# Core_nRF52840.net
KiCad netlist of a schematic drawn in Altium Designer
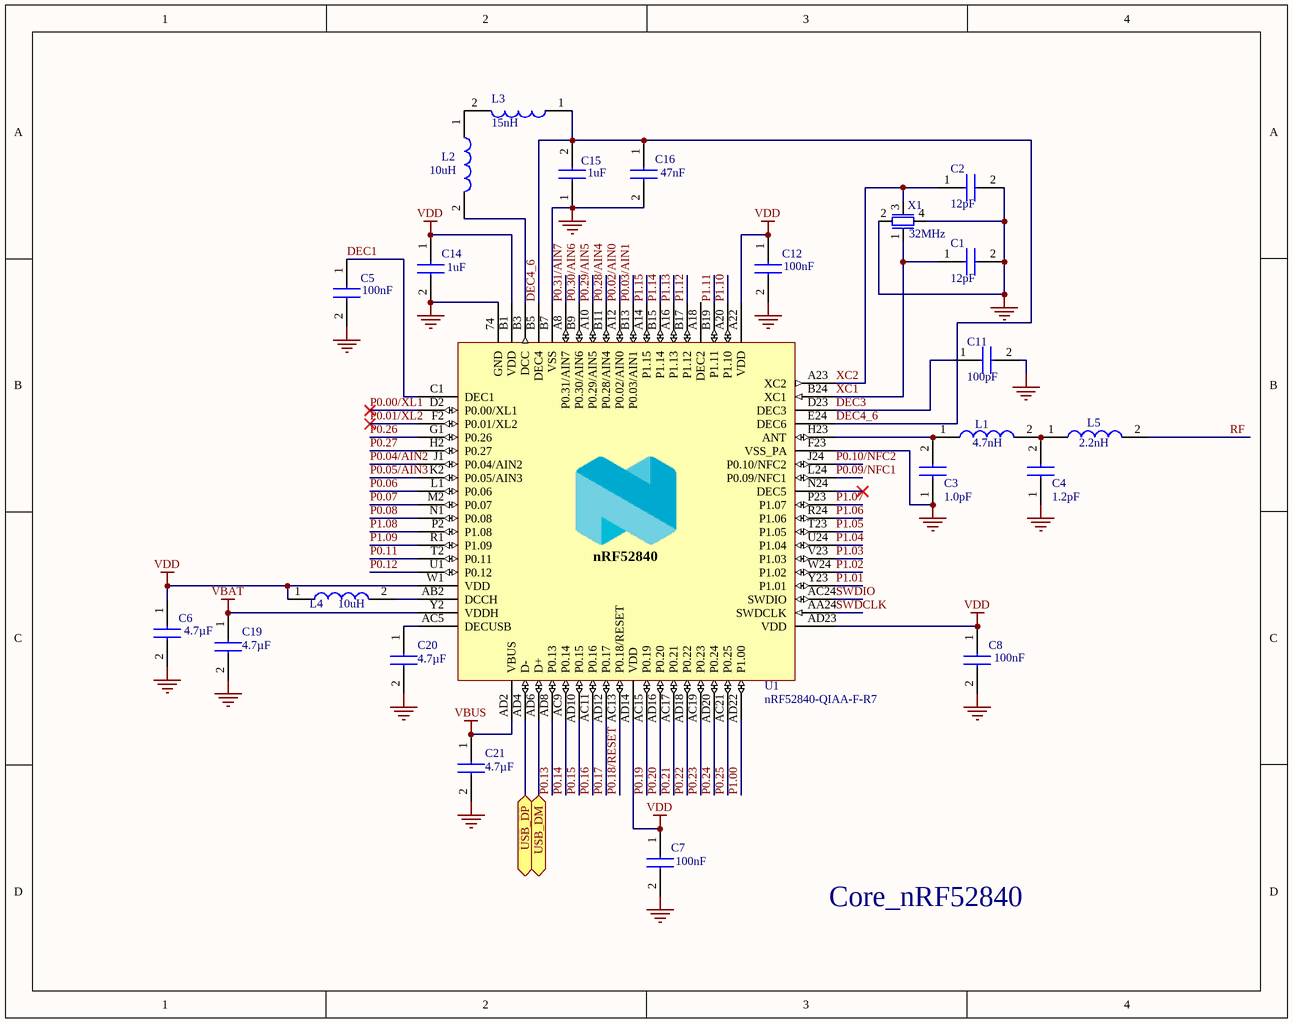
[diagram p0: Core_nRF52840.SchDoc]

(export (version "E")
  (design (tool "Eeschema 10.0.6"))
  (components
    (comp (ref "C1")
      (value "12pF")
      (footprint "BoatRC:GCM155")
      (description "12 pF C0G ±1% 50 V")
      (fields (field (name "MANUFACTURER_PART_NUMBER") "GCM1555C1H120FA16D"))
      (libsource (lib "BoatRC") (part "C_12pF_0402_C0G_1pct"))
    )
    (comp (ref "C2")
      (value "12pF")
      (footprint "BoatRC:GCM155")
      (description "12 pF C0G ±1% 50 V")
      (fields (field (name "MANUFACTURER_PART_NUMBER") "GCM1555C1H120FA16D"))
      (libsource (lib "BoatRC") (part "C_12pF_0402_C0G_1pct"))
    )
    (comp (ref "C3")
      (value "1.0pF")
      (footprint "BoatRC:CAPC1005X55N")
      (description "1.0 pF C0G ±0.05 pF high-Q")
      (fields (field (name "MANUFACTURER_PART_NUMBER") "GJM1555C1H1R0WB01D"))
      (libsource (lib "BoatRC") (part "C_1p0pF_0402_C0G_HQ"))
    )
    (comp (ref "C4")
      (value "1.2pF")
      (footprint "BoatRC:CAPC1005X55N")
      (description "1.2 pF C0G ±0.05 pF high-Q")
      (fields (field (name "MANUFACTURER_PART_NUMBER") "GJM1555C1H1R2WB01D"))
      (libsource (lib "BoatRC") (part "C_1p2pF_0402_C0G_HQ"))
    )
    (comp (ref "C5")
      (value "100nF")
      (footprint "BoatRC:RESC1005X55N")
      (description "100 nF X7R ±10% 50 V")
      (fields (field (name "MANUFACTURER_PART_NUMBER") "CL05B104KB54PNC"))
      (libsource (lib "BoatRC") (part "C_100nF_0402_X7R_50V"))
    )
    (comp (ref "C6")
      (value "4.7µF")
      (footprint "BoatRC:GRM18x")
      (description "4.7 µF X7R ±10% 16 V")
      (fields (field (name "MANUFACTURER_PART_NUMBER") "GRM188Z71C475KE21D"))
      (libsource (lib "BoatRC") (part "C_4u7F_0603_X7R_16V"))
    )
    (comp (ref "C7")
      (value "100nF")
      (footprint "BoatRC:RESC1005X55N")
      (description "100 nF X7R ±10% 50 V")
      (fields (field (name "MANUFACTURER_PART_NUMBER") "CL05B104KB54PNC"))
      (libsource (lib "BoatRC") (part "C_100nF_0402_X7R_50V"))
    )
    (comp (ref "C8")
      (value "100nF")
      (footprint "BoatRC:RESC1005X55N")
      (description "100 nF X7R ±10% 50 V")
      (fields (field (name "MANUFACTURER_PART_NUMBER") "CL05B104KB54PNC"))
      (libsource (lib "BoatRC") (part "C_100nF_0402_X7R_50V"))
    )
    (comp (ref "C11")
      (value "100pF")
      (footprint "BoatRC:CAPC1005X55N")
      (description "100 pF C0G ±5% 50 V")
      (fields (field (name "MANUFACTURER_PART_NUMBER") "0402CG101J500NT"))
      (libsource (lib "BoatRC") (part "C_100pF_0402_C0G"))
    )
    (comp (ref "C12")
      (value "100nF")
      (footprint "BoatRC:RESC1005X55N")
      (description "100 nF X7R ±10% 50 V")
      (fields (field (name "MANUFACTURER_PART_NUMBER") "CL05B104KB54PNC"))
      (libsource (lib "BoatRC") (part "C_100nF_0402_X7R_50V"))
    )
    (comp (ref "C14")
      (value "1uF")
      (footprint "BoatRC:CAPC1608X95N")
      (description "1.0 µF X7R ±10% 50 V")
      (fields (field (name "MANUFACTURER_PART_NUMBER") "CL10B105KB8NQNC"))
      (libsource (lib "BoatRC") (part "C_1uF_0603_X7R_50V"))
    )
    (comp (ref "C15")
      (value "1uF")
      (footprint "BoatRC:CAPC1608X95N")
      (description "1.0 µF X7R ±10% 50 V")
      (fields (field (name "MANUFACTURER_PART_NUMBER") "CL10B105KB8NQNC"))
      (libsource (lib "BoatRC") (part "C_1uF_0603_X7R_50V"))
    )
    (comp (ref "C16")
      (value "47nF")
      (footprint "BoatRC:CAPC1005X55N")
      (description "47 nF X7R ±10% 50 V")
      (fields (field (name "MANUFACTURER_PART_NUMBER") "CC0402KRX7R9BB473"))
      (libsource (lib "BoatRC") (part "C_47nF_0402_X7R_50V"))
    )
    (comp (ref "C19")
      (value "4.7µF")
      (footprint "BoatRC:GRM18x")
      (description "4.7 µF X7R ±10% 16 V")
      (fields (field (name "MANUFACTURER_PART_NUMBER") "GRM188Z71C475KE21D"))
      (libsource (lib "BoatRC") (part "C_4u7F_0603_X7R_16V"))
    )
    (comp (ref "C20")
      (value "4.7µF")
      (footprint "BoatRC:GRM18x")
      (description "4.7 µF X7R ±10% 16 V")
      (fields (field (name "MANUFACTURER_PART_NUMBER") "GRM188Z71C475KE21D"))
      (libsource (lib "BoatRC") (part "C_4u7F_0603_X7R_16V"))
    )
    (comp (ref "C21")
      (value "4.7µF")
      (footprint "BoatRC:GRM18x")
      (description "4.7 µF X7R ±10% 16 V")
      (fields (field (name "MANUFACTURER_PART_NUMBER") "GRM188Z71C475KE21D"))
      (libsource (lib "BoatRC") (part "C_4u7F_0603_X7R_16V"))
    )
    (comp (ref "L1")
      (value "4.7nH")
      (footprint "BoatRC:LQG15WH0N7B02D")
      (description "4.7 nH ±0.1 nH RF")
      (fields (field (name "MANUFACTURER_PART_NUMBER") "LQG15HN4N7B02D"))
      (libsource (lib "BoatRC") (part "L_4n7H_0402_RF"))
    )
    (comp (ref "L2")
      (value "10uH")
      (footprint "BoatRC:CAPC1608X95N")
      (description "10 µH ±20%, 400 mA, 0.55 Ω")
      (fields (field (name "MANUFACTURER_PART_NUMBER") "MGFL1608F100MT-LF"))
      (libsource (lib "BoatRC") (part "L_10uH_0603"))
    )
    (comp (ref "L3")
      (value "15nH")
      (footprint "BoatRC:LQG15WH0N7B02D")
      (description "15 nH ±5%, 450 mA")
      (fields (field (name "MANUFACTURER_PART_NUMBER") "LQG15HS2N2B02D"))
      (libsource (lib "BoatRC") (part "L_15nH_0402"))
    )
    (comp (ref "L4")
      (value "10uH")
      (footprint "BoatRC:CAPC1608X95N")
      (description "10 µH ±20%, 400 mA, 0.55 Ω")
      (fields (field (name "MANUFACTURER_PART_NUMBER") "MGFL1608F100MT-LF"))
      (libsource (lib "BoatRC") (part "L_10uH_0603"))
    )
    (comp (ref "L5")
      (value "2.2nH")
      (footprint "BoatRC:LQG15WH0N7B02D")
      (description "2.2 nH ±0.1 nH RF")
      (fields (field (name "MANUFACTURER_PART_NUMBER") "LQG15HS15NJ02D"))
      (libsource (lib "BoatRC") (part "L_2n2H_0402_RF"))
    )
    (comp (ref "U1")
      (value "nRF52840-QIAA-F-R7")
      (footprint "AQFN50P700X700X85_HS-74N")
      (description "Multi-protocol Bluetooth Low Energy, IEEE 802.15.4, ANT and 2.4GHz proprietary system-on-chip")
      (fields
        (field (name "MANUFACTURER") "Nordic Semiconductor")
        (field (name "DIGIKEY PART NUMBER") "4823-NRF52840-QIAA-F-R7CT-ND")
      )
      (libsource (lib "BoatRC") (part "nRF52840-QIAA-F-R7"))
    )
    (comp (ref "X1")
      (value "32MHz")
      (footprint "BoatRC:X201632MKB4SI")
      (description "32 MHz, 8 pF, ±10/±20 ppm")
      (fields (field (name "MANUFACTURER_PART_NUMBER") "X201632MKB4SI"))
      (libsource (lib "BoatRC") (part "Y_32MHz_2016_8pF"))
    )
  )
  (nets
    (net (code "1") (name "/DEC1") (class "Default")
      (node (ref "C5") (pin "1") (pinfunction "1_1") (pintype "passive"))
      (node (ref "U1") (pin "C1") (pinfunction "DEC1_C1") (pintype "power_in"))
    )
    (net (code "2") (name "/DEC3") (class "Default")
      (node (ref "C11") (pin "1") (pinfunction "1_1") (pintype "passive"))
      (node (ref "U1") (pin "D23") (pinfunction "DEC3_D23") (pintype "power_in"))
    )
    (net (code "3") (name "/DEC4_6") (class "Default")
      (node (ref "C15") (pin "2") (pinfunction "2_2") (pintype "passive"))
      (node (ref "C16") (pin "1") (pinfunction "1_1") (pintype "passive"))
      (node (ref "L3") (pin "1") (pinfunction "1_1") (pintype "passive"))
      (node (ref "U1") (pin "B5") (pinfunction "DEC4_B5") (pintype "power_in"))
      (node (ref "U1") (pin "E24") (pinfunction "DEC6_E24") (pintype "power_in"))
    )
    (net (code "4") (name "/P0.00{slash}XL1") (class "Default")
      (node (ref "U1") (pin "D2") (pinfunction "P0.00/XL1_D2") (pintype "bidirectional+no_connect"))
    )
    (net (code "5") (name "/P0.01{slash}XL2") (class "Default")
      (node (ref "U1") (pin "F2") (pinfunction "P0.01/XL2_F2") (pintype "bidirectional+no_connect"))
    )
    (net (code "6") (name "/P0.02{slash}AIN0") (class "Default")
      (node (ref "U1") (pin "A12") (pinfunction "P0.02/AIN0_A12") (pintype "bidirectional"))
    )
    (net (code "7") (name "/P0.03{slash}AIN1") (class "Default")
      (node (ref "U1") (pin "B13") (pinfunction "P0.03/AIN1_B13") (pintype "bidirectional"))
    )
    (net (code "8") (name "/P0.04{slash}AIN2") (class "Default")
      (node (ref "U1") (pin "J1") (pinfunction "P0.04/AIN2_J1") (pintype "bidirectional"))
    )
    (net (code "9") (name "/P0.05{slash}AIN3") (class "Default")
      (node (ref "U1") (pin "K2") (pinfunction "P0.05/AIN3_K2") (pintype "bidirectional"))
    )
    (net (code "10") (name "/P0.06") (class "Default")
      (node (ref "U1") (pin "L1") (pinfunction "P0.06_L1") (pintype "bidirectional"))
    )
    (net (code "11") (name "/P0.07") (class "Default")
      (node (ref "U1") (pin "M2") (pinfunction "P0.07_M2") (pintype "bidirectional"))
    )
    (net (code "12") (name "/P0.08") (class "Default")
      (node (ref "U1") (pin "N1") (pinfunction "P0.08_N1") (pintype "bidirectional"))
    )
    (net (code "13") (name "/P0.09{slash}NFC1") (class "Default")
      (node (ref "U1") (pin "L24") (pinfunction "P0.09/NFC1_L24") (pintype "bidirectional"))
    )
    (net (code "14") (name "/P0.10{slash}NFC2") (class "Default")
      (node (ref "U1") (pin "J24") (pinfunction "P0.10/NFC2_J24") (pintype "bidirectional"))
    )
    (net (code "15") (name "/P0.11") (class "Default")
      (node (ref "U1") (pin "T2") (pinfunction "P0.11_T2") (pintype "bidirectional"))
    )
    (net (code "16") (name "/P0.12") (class "Default")
      (node (ref "U1") (pin "U1") (pinfunction "P0.12_U1") (pintype "bidirectional"))
    )
    (net (code "17") (name "/P0.13") (class "Default")
      (node (ref "U1") (pin "AD8") (pinfunction "P0.13_AD8") (pintype "bidirectional"))
    )
    (net (code "18") (name "/P0.14") (class "Default")
      (node (ref "U1") (pin "AC9") (pinfunction "P0.14_AC9") (pintype "bidirectional"))
    )
    (net (code "19") (name "/P0.15") (class "Default")
      (node (ref "U1") (pin "AD10") (pinfunction "P0.15_AD10") (pintype "bidirectional"))
    )
    (net (code "20") (name "/P0.16") (class "Default")
      (node (ref "U1") (pin "AC11") (pinfunction "P0.16_AC11") (pintype "bidirectional"))
    )
    (net (code "21") (name "/P0.17") (class "Default")
      (node (ref "U1") (pin "AD12") (pinfunction "P0.17_AD12") (pintype "bidirectional"))
    )
    (net (code "22") (name "/P0.18{slash}RESET") (class "Default")
      (node (ref "U1") (pin "AC13") (pinfunction "P0.18/RESET_AC13") (pintype "bidirectional"))
    )
    (net (code "23") (name "/P0.19") (class "Default")
      (node (ref "U1") (pin "AC15") (pinfunction "P0.19_AC15") (pintype "bidirectional"))
    )
    (net (code "24") (name "/P0.20") (class "Default")
      (node (ref "U1") (pin "AD16") (pinfunction "P0.20_AD16") (pintype "bidirectional"))
    )
    (net (code "25") (name "/P0.21") (class "Default")
      (node (ref "U1") (pin "AC17") (pinfunction "P0.21_AC17") (pintype "bidirectional"))
    )
    (net (code "26") (name "/P0.22") (class "Default")
      (node (ref "U1") (pin "AD18") (pinfunction "P0.22_AD18") (pintype "bidirectional"))
    )
    (net (code "27") (name "/P0.23") (class "Default")
      (node (ref "U1") (pin "AC19") (pinfunction "P0.23_AC19") (pintype "bidirectional"))
    )
    (net (code "28") (name "/P0.24") (class "Default")
      (node (ref "U1") (pin "AD20") (pinfunction "P0.24_AD20") (pintype "bidirectional"))
    )
    (net (code "29") (name "/P0.25") (class "Default")
      (node (ref "U1") (pin "AC21") (pinfunction "P0.25_AC21") (pintype "bidirectional"))
    )
    (net (code "30") (name "/P0.26") (class "Default")
      (node (ref "U1") (pin "G1") (pinfunction "P0.26_G1") (pintype "bidirectional"))
    )
    (net (code "31") (name "/P0.27") (class "Default")
      (node (ref "U1") (pin "H2") (pinfunction "P0.27_H2") (pintype "bidirectional"))
    )
    (net (code "32") (name "/P0.28{slash}AIN4") (class "Default")
      (node (ref "U1") (pin "B11") (pinfunction "P0.28/AIN4_B11") (pintype "bidirectional"))
    )
    (net (code "33") (name "/P0.29{slash}AIN5") (class "Default")
      (node (ref "U1") (pin "A10") (pinfunction "P0.29/AIN5_A10") (pintype "bidirectional"))
    )
    (net (code "34") (name "/P0.30{slash}AIN6") (class "Default")
      (node (ref "U1") (pin "B9") (pinfunction "P0.30/AIN6_B9") (pintype "bidirectional"))
    )
    (net (code "35") (name "/P0.31{slash}AIN7") (class "Default")
      (node (ref "U1") (pin "A8") (pinfunction "P0.31/AIN7_A8") (pintype "bidirectional"))
    )
    (net (code "36") (name "/P1.00") (class "Default")
      (node (ref "U1") (pin "AD22") (pinfunction "P1.00_AD22") (pintype "bidirectional"))
    )
    (net (code "37") (name "/P1.01") (class "Default")
      (node (ref "U1") (pin "Y23") (pinfunction "P1.01_Y23") (pintype "bidirectional"))
    )
    (net (code "38") (name "/P1.02") (class "Default")
      (node (ref "U1") (pin "W24") (pinfunction "P1.02_W24") (pintype "bidirectional"))
    )
    (net (code "39") (name "/P1.03") (class "Default")
      (node (ref "U1") (pin "V23") (pinfunction "P1.03_V23") (pintype "bidirectional"))
    )
    (net (code "40") (name "/P1.04") (class "Default")
      (node (ref "U1") (pin "U24") (pinfunction "P1.04_U24") (pintype "bidirectional"))
    )
    (net (code "41") (name "/P1.05") (class "Default")
      (node (ref "U1") (pin "T23") (pinfunction "P1.05_T23") (pintype "bidirectional"))
    )
    (net (code "42") (name "/P1.06") (class "Default")
      (node (ref "U1") (pin "R24") (pinfunction "P1.06_R24") (pintype "bidirectional"))
    )
    (net (code "43") (name "/P1.07") (class "Default")
      (node (ref "U1") (pin "P23") (pinfunction "P1.07_P23") (pintype "bidirectional"))
    )
    (net (code "44") (name "/P1.08") (class "Default")
      (node (ref "U1") (pin "P2") (pinfunction "P1.08_P2") (pintype "bidirectional"))
    )
    (net (code "45") (name "/P1.09") (class "Default")
      (node (ref "U1") (pin "R1") (pinfunction "P1.09_R1") (pintype "bidirectional"))
    )
    (net (code "46") (name "/P1.10") (class "Default")
      (node (ref "U1") (pin "A20") (pinfunction "P1.10_A20") (pintype "bidirectional"))
    )
    (net (code "47") (name "/P1.11") (class "Default")
      (node (ref "U1") (pin "B19") (pinfunction "P1.11_B19") (pintype "bidirectional"))
    )
    (net (code "48") (name "/P1.12") (class "Default")
      (node (ref "U1") (pin "B17") (pinfunction "P1.12_B17") (pintype "bidirectional"))
    )
    (net (code "49") (name "/P1.13") (class "Default")
      (node (ref "U1") (pin "A16") (pinfunction "P1.13_A16") (pintype "bidirectional"))
    )
    (net (code "50") (name "/P1.14") (class "Default")
      (node (ref "U1") (pin "B15") (pinfunction "P1.14_B15") (pintype "bidirectional"))
    )
    (net (code "51") (name "/P1.15") (class "Default")
      (node (ref "U1") (pin "A14") (pinfunction "P1.15_A14") (pintype "bidirectional"))
    )
    (net (code "52") (name "/RF") (class "Default")
      (node (ref "L5") (pin "2") (pinfunction "2_2") (pintype "passive"))
    )
    (net (code "53") (name "/SWDCLK") (class "Default")
      (node (ref "U1") (pin "AA24") (pinfunction "SWDCLK_AA24") (pintype "input"))
    )
    (net (code "54") (name "/SWDIO") (class "Default")
      (node (ref "U1") (pin "AC24") (pinfunction "SWDIO_AC24") (pintype "bidirectional"))
    )
    (net (code "55") (name "/USB_DM") (class "Default")
      (node (ref "U1") (pin "AD6") (pinfunction "D+_AD6") (pintype "bidirectional"))
    )
    (net (code "56") (name "/USB_DP") (class "Default")
      (node (ref "U1") (pin "AD4") (pinfunction "D-_AD4") (pintype "bidirectional"))
    )
    (net (code "57") (name "/XC1") (class "Default")
      (node (ref "C1") (pin "1") (pinfunction "1_1") (pintype "passive"))
      (node (ref "U1") (pin "B24") (pinfunction "XC1_B24") (pintype "input"))
      (node (ref "X1") (pin "1") (pinfunction "inp_1") (pintype "passive"))
    )
    (net (code "58") (name "/XC2") (class "Default")
      (node (ref "C2") (pin "1") (pinfunction "1_1") (pintype "passive"))
      (node (ref "U1") (pin "A23") (pinfunction "XC2_A23") (pintype "output"))
      (node (ref "X1") (pin "3") (pinfunction "out_3") (pintype "passive"))
    )
    (net (code "59") (name "GND") (class "Default")
      (node (ref "C1") (pin "2") (pinfunction "2_2") (pintype "passive"))
      (node (ref "C11") (pin "2") (pinfunction "2_2") (pintype "passive"))
      (node (ref "C12") (pin "2") (pinfunction "2_2") (pintype "passive"))
      (node (ref "C14") (pin "2") (pinfunction "2_2") (pintype "passive"))
      (node (ref "C15") (pin "1") (pinfunction "1_1") (pintype "passive"))
      (node (ref "C16") (pin "2") (pinfunction "2_2") (pintype "passive"))
      (node (ref "C19") (pin "2") (pinfunction "2_2") (pintype "passive"))
      (node (ref "C2") (pin "2") (pinfunction "2_2") (pintype "passive"))
      (node (ref "C20") (pin "2") (pinfunction "2_2") (pintype "passive"))
      (node (ref "C21") (pin "2") (pinfunction "2_2") (pintype "passive"))
      (node (ref "C3") (pin "1") (pinfunction "1_1") (pintype "passive"))
      (node (ref "C4") (pin "1") (pinfunction "1_1") (pintype "passive"))
      (node (ref "C5") (pin "2") (pinfunction "2_2") (pintype "passive"))
      (node (ref "C6") (pin "2") (pinfunction "2_2") (pintype "passive"))
      (node (ref "C7") (pin "2") (pinfunction "2_2") (pintype "passive"))
      (node (ref "C8") (pin "2") (pinfunction "2_2") (pintype "passive"))
      (node (ref "U1") (pin "74") (pinfunction "GND_74") (pintype "power_in"))
      (node (ref "U1") (pin "B7") (pinfunction "VSS_B7") (pintype "power_in"))
      (node (ref "U1") (pin "F23") (pinfunction "VSS_PA_F23") (pintype "power_in"))
      (node (ref "X1") (pin "2") (pinfunction "GND_2") (pintype "passive"))
      (node (ref "X1") (pin "4") (pinfunction "GND_4") (pintype "passive"))
    )
    (net (code "60") (name "Net-(C4-Pad2)") (class "Default")
      (node (ref "C4") (pin "2") (pinfunction "2_2") (pintype "passive"))
      (node (ref "L1") (pin "2") (pinfunction "2_2") (pintype "passive"))
      (node (ref "L5") (pin "1") (pinfunction "1_1") (pintype "passive"))
    )
    (net (code "61") (name "Net-(L2-Pad1)") (class "Default")
      (node (ref "L2") (pin "1") (pinfunction "1_1") (pintype "passive"))
      (node (ref "L3") (pin "2") (pinfunction "2_2") (pintype "passive"))
    )
    (net (code "62") (name "Net-(U1-ANT)") (class "Default")
      (node (ref "C3") (pin "2") (pinfunction "2_2") (pintype "passive"))
      (node (ref "L1") (pin "1") (pinfunction "1_1") (pintype "passive"))
      (node (ref "U1") (pin "H23") (pinfunction "ANT_H23") (pintype "bidirectional"))
    )
    (net (code "63") (name "Net-(U1-DCC)") (class "Default")
      (node (ref "L2") (pin "2") (pinfunction "2_2") (pintype "passive"))
      (node (ref "U1") (pin "B3") (pinfunction "DCC_B3") (pintype "output"))
    )
    (net (code "64") (name "Net-(U1-DCCH)") (class "Default")
      (node (ref "L4") (pin "2") (pinfunction "2_2") (pintype "passive"))
      (node (ref "U1") (pin "AB2") (pinfunction "DCCH_AB2") (pintype "power_in"))
    )
    (net (code "65") (name "Net-(U1-DECUSB)") (class "Default")
      (node (ref "C20") (pin "1") (pinfunction "1_1") (pintype "passive"))
      (node (ref "U1") (pin "AC5") (pinfunction "DECUSB_AC5") (pintype "power_in"))
    )
    (net (code "66") (name "VBAT") (class "Default")
      (node (ref "C19") (pin "1") (pinfunction "1_1") (pintype "passive"))
      (node (ref "U1") (pin "Y2") (pinfunction "VDDH_Y2") (pintype "power_in"))
    )
    (net (code "67") (name "VBUS") (class "Default")
      (node (ref "C21") (pin "1") (pinfunction "1_1") (pintype "passive"))
      (node (ref "U1") (pin "AD2") (pinfunction "VBUS_AD2") (pintype "power_in"))
    )
    (net (code "68") (name "VDD") (class "Default")
      (node (ref "C12") (pin "1") (pinfunction "1_1") (pintype "passive"))
      (node (ref "C14") (pin "1") (pinfunction "1_1") (pintype "passive"))
      (node (ref "C6") (pin "1") (pinfunction "1_1") (pintype "passive"))
      (node (ref "C7") (pin "1") (pinfunction "1_1") (pintype "passive"))
      (node (ref "C8") (pin "1") (pinfunction "1_1") (pintype "passive"))
      (node (ref "L4") (pin "1") (pinfunction "1_1") (pintype "passive"))
      (node (ref "U1") (pin "A22") (pinfunction "VDD_A22") (pintype "power_in"))
      (node (ref "U1") (pin "AD14") (pinfunction "VDD_AD14") (pintype "power_in"))
      (node (ref "U1") (pin "AD23") (pinfunction "VDD_AD23") (pintype "power_in"))
      (node (ref "U1") (pin "B1") (pinfunction "VDD_B1") (pintype "power_in"))
      (node (ref "U1") (pin "W1") (pinfunction "VDD_W1") (pintype "power_in"))
    )
    (net (code "69") (name "unconnected-(U1-DEC2-PadA18)") (class "Default")
      (node (ref "U1") (pin "A18") (pinfunction "DEC2_A18") (pintype "power_in"))
    )
    (net (code "70") (name "unconnected-(U1-DEC5-PadN24)") (class "Default")
      (node (ref "U1") (pin "N24") (pinfunction "DEC5_N24") (pintype "power_in+no_connect"))
    )
  )
)
